# stm32f4stampV1_3_1.net
KiCad netlist of a schematic drawn in EAGLE
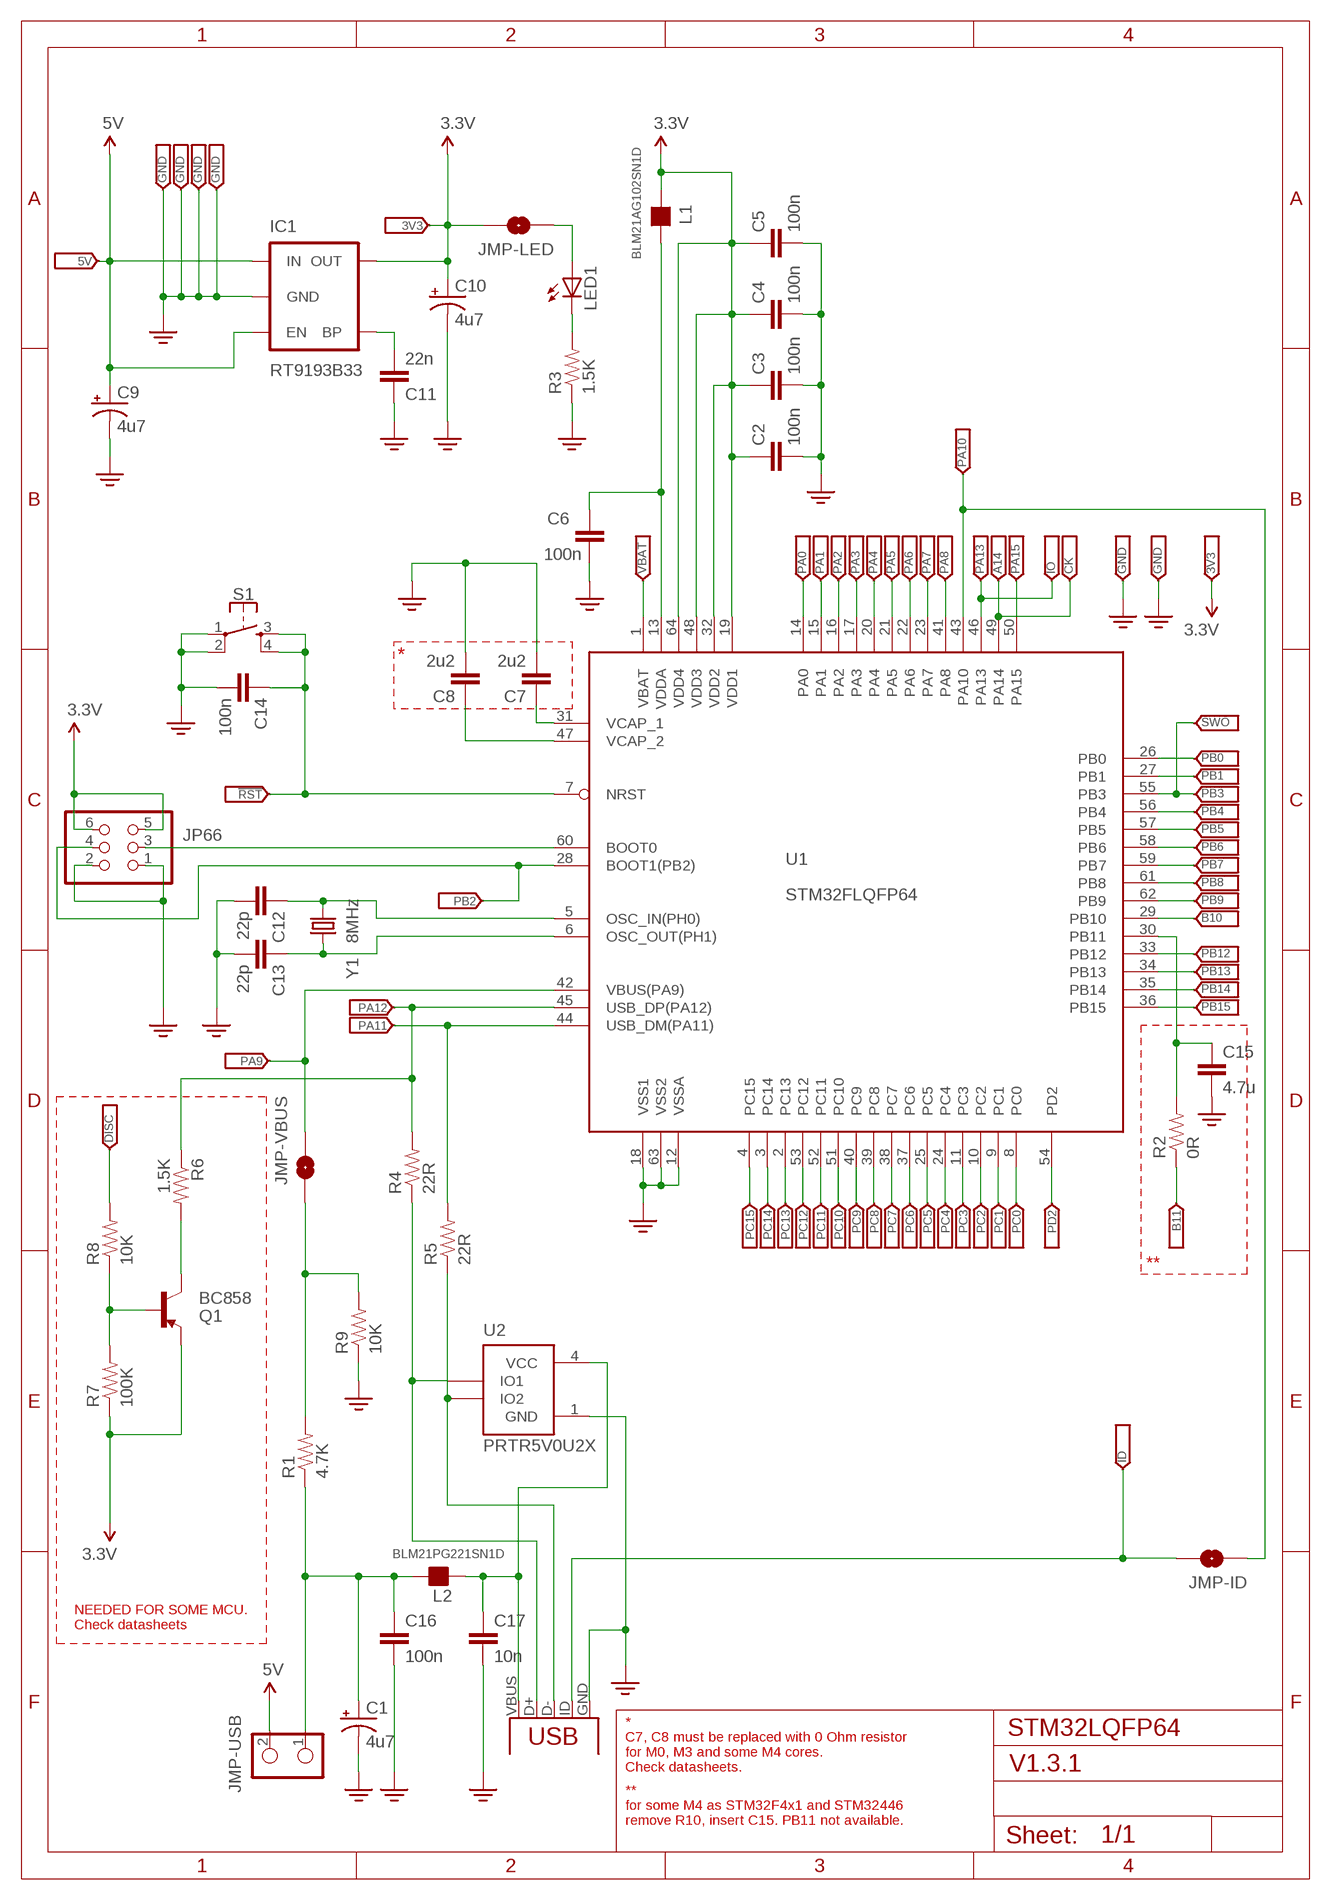
[diagram p0: schematic, sheet 1]

(export (version "E")
  (design (tool "Eeschema 10.0.6"))
  (components
    (comp (ref "C1")
      (value "4u7")
      (footprint "eagle-import:EIA3216-KIT")
      (libsource (lib "eagle-import") (part "CAP_POL1206-KIT"))
    )
    (comp (ref "C2")
      (value "100n")
      (footprint "eagle-import:0805")
      (libsource (lib "eagle-import") (part "CAP0805"))
    )
    (comp (ref "C3")
      (value "100n")
      (footprint "eagle-import:0805")
      (libsource (lib "eagle-import") (part "CAP0805"))
    )
    (comp (ref "C4")
      (value "100n")
      (footprint "eagle-import:0805")
      (libsource (lib "eagle-import") (part "CAP0805"))
    )
    (comp (ref "C5")
      (value "100n")
      (footprint "eagle-import:0805")
      (libsource (lib "eagle-import") (part "CAP0805"))
    )
    (comp (ref "C6")
      (value "100n")
      (footprint "eagle-import:0805")
      (libsource (lib "eagle-import") (part "CAP0805"))
    )
    (comp (ref "C7")
      (value "2u2")
      (footprint "eagle-import:0805")
      (libsource (lib "eagle-import") (part "CAP0805"))
    )
    (comp (ref "C8")
      (value "2u2")
      (footprint "eagle-import:0805")
      (libsource (lib "eagle-import") (part "CAP0805"))
    )
    (comp (ref "C9")
      (value "4u7")
      (footprint "eagle-import:EIA3216-KIT")
      (libsource (lib "eagle-import") (part "CAP_POL1206-KIT"))
    )
    (comp (ref "C10")
      (value "4u7")
      (footprint "eagle-import:EIA3216-KIT")
      (libsource (lib "eagle-import") (part "CAP_POL1206-KIT"))
    )
    (comp (ref "C11")
      (value "22n")
      (footprint "eagle-import:0805")
      (libsource (lib "eagle-import") (part "CAP0805"))
    )
    (comp (ref "C12")
      (value "22p")
      (footprint "eagle-import:0805")
      (libsource (lib "eagle-import") (part "CAP0805"))
    )
    (comp (ref "C13")
      (value "22p")
      (footprint "eagle-import:0805")
      (libsource (lib "eagle-import") (part "CAP0805"))
    )
    (comp (ref "C14")
      (value "100n")
      (footprint "eagle-import:0805")
      (libsource (lib "eagle-import") (part "CAP0805"))
    )
    (comp (ref "C15")
      (value "4.7u")
      (footprint "eagle-import:0805")
      (libsource (lib "eagle-import") (part "CAP0805"))
    )
    (comp (ref "C16")
      (value "100n")
      (footprint "eagle-import:0805")
      (libsource (lib "eagle-import") (part "CAP0805"))
    )
    (comp (ref "C17")
      (value "10n")
      (footprint "eagle-import:0805")
      (libsource (lib "eagle-import") (part "CAP0805"))
    )
    (comp (ref "IC1")
      (value "RT9193B33")
      (footprint "eagle-import:SOT23-5")
      (libsource (lib "eagle-import") (part "V_REG_LDOSMD"))
    )
    (comp (ref "JMP-ID")
      (value "SOLDERJUMPERNO")
      (footprint "eagle-import:SJ_2S-NO")
      (libsource (lib "eagle-import") (part "SOLDERJUMPERNO"))
    )
    (comp (ref "JMP-LED")
      (value "SOLDERJUMPERNO")
      (footprint "eagle-import:SJ_2S-NO")
      (libsource (lib "eagle-import") (part "SOLDERJUMPERNO"))
    )
    (comp (ref "JMP-USB")
      (value "JUMPER-2PTH")
      (footprint "eagle-import:1X02")
      (libsource (lib "eagle-import") (part "JUMPER-2PTH"))
    )
    (comp (ref "JMP-VBUS")
      (value "SOLDERJUMPERNO")
      (footprint "eagle-import:SJ_2S-NO")
      (libsource (lib "eagle-import") (part "SOLDERJUMPERNO"))
    )
    (comp (ref "JP1")
      (value "PA12")
      (footprint "eagle-import:1X1-HEADER-HOLE")
      (libsource (lib "eagle-import") (part "HEADERHOLE-HEADERHOLE"))
    )
    (comp (ref "JP2")
      (value "5V")
      (footprint "eagle-import:1X1-HEADER-HOLE")
      (libsource (lib "eagle-import") (part "HEADERHOLE-HEADERHOLE"))
    )
    (comp (ref "JP3")
      (value "GND")
      (footprint "eagle-import:1X1-HEADER-HOLE")
      (libsource (lib "eagle-import") (part "HEADERHOLE-HEADERHOLE"))
    )
    (comp (ref "JP4")
      (value "3V3")
      (footprint "eagle-import:1X1-HEADER-HOLE")
      (libsource (lib "eagle-import") (part "HEADERHOLE-HEADERHOLE"))
    )
    (comp (ref "JP5")
      (value "DISC")
      (footprint "eagle-import:1X1-HEADER-HOLE")
      (libsource (lib "eagle-import") (part "HEADERHOLE-HEADERHOLE"))
    )
    (comp (ref "JP6")
      (value "GND")
      (footprint "eagle-import:1X1-HEADER-HOLE")
      (libsource (lib "eagle-import") (part "HEADERHOLE-HEADERHOLE"))
    )
    (comp (ref "JP7")
      (value "GND")
      (footprint "eagle-import:1X1-HEADER-HOLE")
      (libsource (lib "eagle-import") (part "HEADERHOLE-HEADERHOLE"))
    )
    (comp (ref "JP8")
      (value "PB8")
      (footprint "eagle-import:1X1-HEADER-HOLE")
      (libsource (lib "eagle-import") (part "HEADERHOLE-HEADERHOLE"))
    )
    (comp (ref "JP9")
      (value "PA10")
      (footprint "eagle-import:1X1-HEADER-HOLE")
      (libsource (lib "eagle-import") (part "HEADERHOLE-HEADERHOLE"))
    )
    (comp (ref "JP10")
      (value "PA8")
      (footprint "eagle-import:1X1-HEADER-HOLE")
      (libsource (lib "eagle-import") (part "HEADERHOLE-HEADERHOLE"))
    )
    (comp (ref "JP11")
      (value "PA13")
      (footprint "eagle-import:1X1-HEADER-HOLE")
      (libsource (lib "eagle-import") (part "HEADERHOLE-HEADERHOLE"))
    )
    (comp (ref "JP12")
      (value "PC9")
      (footprint "eagle-import:1X1-HEADER-HOLE")
      (libsource (lib "eagle-import") (part "HEADERHOLE-HEADERHOLE"))
    )
    (comp (ref "JP13")
      (value "PC15")
      (footprint "eagle-import:1X1-HEADER-HOLE")
      (libsource (lib "eagle-import") (part "HEADERHOLE-HEADERHOLE"))
    )
    (comp (ref "JP14")
      (value "PC14")
      (footprint "eagle-import:1X1-HEADER-HOLE")
      (libsource (lib "eagle-import") (part "HEADERHOLE-HEADERHOLE"))
    )
    (comp (ref "JP15")
      (value "PC13")
      (footprint "eagle-import:1X1-HEADER-HOLE")
      (libsource (lib "eagle-import") (part "HEADERHOLE-HEADERHOLE"))
    )
    (comp (ref "JP16")
      (value "PC12")
      (footprint "eagle-import:1X1-HEADER-HOLE")
      (libsource (lib "eagle-import") (part "HEADERHOLE-HEADERHOLE"))
    )
    (comp (ref "JP17")
      (value "PC11")
      (footprint "eagle-import:1X1-HEADER-HOLE")
      (libsource (lib "eagle-import") (part "HEADERHOLE-HEADERHOLE"))
    )
    (comp (ref "JP18")
      (value "PC10")
      (footprint "eagle-import:1X1-HEADER-HOLE")
      (libsource (lib "eagle-import") (part "HEADERHOLE-HEADERHOLE"))
    )
    (comp (ref "JP19")
      (value "PC8")
      (footprint "eagle-import:1X1-HEADER-HOLE")
      (libsource (lib "eagle-import") (part "HEADERHOLE-HEADERHOLE"))
    )
    (comp (ref "JP20")
      (value "PC7")
      (footprint "eagle-import:1X1-HEADER-HOLE")
      (libsource (lib "eagle-import") (part "HEADERHOLE-HEADERHOLE"))
    )
    (comp (ref "JP21")
      (value "PC6")
      (footprint "eagle-import:1X1-HEADER-HOLE")
      (libsource (lib "eagle-import") (part "HEADERHOLE-HEADERHOLE"))
    )
    (comp (ref "JP22")
      (value "PC5")
      (footprint "eagle-import:1X1-HEADER-HOLE")
      (libsource (lib "eagle-import") (part "HEADERHOLE-HEADERHOLE"))
    )
    (comp (ref "JP23")
      (value "PC4")
      (footprint "eagle-import:1X1-HEADER-HOLE")
      (libsource (lib "eagle-import") (part "HEADERHOLE-HEADERHOLE"))
    )
    (comp (ref "JP24")
      (value "PC3")
      (footprint "eagle-import:1X1-HEADER-HOLE")
      (libsource (lib "eagle-import") (part "HEADERHOLE-HEADERHOLE"))
    )
    (comp (ref "JP25")
      (value "PC2")
      (footprint "eagle-import:1X1-HEADER-HOLE")
      (libsource (lib "eagle-import") (part "HEADERHOLE-HEADERHOLE"))
    )
    (comp (ref "JP26")
      (value "PC1")
      (footprint "eagle-import:1X1-HEADER-HOLE")
      (libsource (lib "eagle-import") (part "HEADERHOLE-HEADERHOLE"))
    )
    (comp (ref "JP27")
      (value "PC0")
      (footprint "eagle-import:1X1-HEADER-HOLE")
      (libsource (lib "eagle-import") (part "HEADERHOLE-HEADERHOLE"))
    )
    (comp (ref "JP28")
      (value "PD2")
      (footprint "eagle-import:1X1-HEADER-HOLE")
      (libsource (lib "eagle-import") (part "HEADERHOLE-HEADERHOLE"))
    )
    (comp (ref "JP29")
      (value "PA0")
      (footprint "eagle-import:1X1-HEADER-HOLE")
      (libsource (lib "eagle-import") (part "HEADERHOLE-HEADERHOLE"))
    )
    (comp (ref "JP30")
      (value "PA1")
      (footprint "eagle-import:1X1-HEADER-HOLE")
      (libsource (lib "eagle-import") (part "HEADERHOLE-HEADERHOLE"))
    )
    (comp (ref "JP31")
      (value "PA2")
      (footprint "eagle-import:1X1-HEADER-HOLE")
      (libsource (lib "eagle-import") (part "HEADERHOLE-HEADERHOLE"))
    )
    (comp (ref "JP32")
      (value "PA3")
      (footprint "eagle-import:1X1-HEADER-HOLE")
      (libsource (lib "eagle-import") (part "HEADERHOLE-HEADERHOLE"))
    )
    (comp (ref "JP33")
      (value "PA4")
      (footprint "eagle-import:1X1-HEADER-HOLE")
      (libsource (lib "eagle-import") (part "HEADERHOLE-HEADERHOLE"))
    )
    (comp (ref "JP34")
      (value "PA5")
      (footprint "eagle-import:1X1-HEADER-HOLE")
      (libsource (lib "eagle-import") (part "HEADERHOLE-HEADERHOLE"))
    )
    (comp (ref "JP35")
      (value "PA6")
      (footprint "eagle-import:1X1-HEADER-HOLE")
      (libsource (lib "eagle-import") (part "HEADERHOLE-HEADERHOLE"))
    )
    (comp (ref "JP36")
      (value "PA7")
      (footprint "eagle-import:1X1-HEADER-HOLE")
      (libsource (lib "eagle-import") (part "HEADERHOLE-HEADERHOLE"))
    )
    (comp (ref "JP37")
      (value "A14")
      (footprint "eagle-import:1X1-HEADER-HOLE")
      (libsource (lib "eagle-import") (part "HEADERHOLE-HEADERHOLE"))
    )
    (comp (ref "JP38")
      (value "PA15")
      (footprint "eagle-import:1X1-HEADER-HOLE")
      (libsource (lib "eagle-import") (part "HEADERHOLE-HEADERHOLE"))
    )
    (comp (ref "JP39")
      (value "PB0")
      (footprint "eagle-import:1X1-HEADER-HOLE")
      (libsource (lib "eagle-import") (part "HEADERHOLE-HEADERHOLE"))
    )
    (comp (ref "JP40")
      (value "PB1")
      (footprint "eagle-import:1X1-HEADER-HOLE")
      (libsource (lib "eagle-import") (part "HEADERHOLE-HEADERHOLE"))
    )
    (comp (ref "JP41")
      (value "PB3")
      (footprint "eagle-import:1X1-HEADER-HOLE")
      (libsource (lib "eagle-import") (part "HEADERHOLE-HEADERHOLE"))
    )
    (comp (ref "JP42")
      (value "PB4")
      (footprint "eagle-import:1X1-HEADER-HOLE")
      (libsource (lib "eagle-import") (part "HEADERHOLE-HEADERHOLE"))
    )
    (comp (ref "JP43")
      (value "PB5")
      (footprint "eagle-import:1X1-HEADER-HOLE")
      (libsource (lib "eagle-import") (part "HEADERHOLE-HEADERHOLE"))
    )
    (comp (ref "JP44")
      (value "PB6")
      (footprint "eagle-import:1X1-HEADER-HOLE")
      (libsource (lib "eagle-import") (part "HEADERHOLE-HEADERHOLE"))
    )
    (comp (ref "JP45")
      (value "PB7")
      (footprint "eagle-import:1X1-HEADER-HOLE")
      (libsource (lib "eagle-import") (part "HEADERHOLE-HEADERHOLE"))
    )
    (comp (ref "JP46")
      (value "PB9")
      (footprint "eagle-import:1X1-HEADER-HOLE")
      (libsource (lib "eagle-import") (part "HEADERHOLE-HEADERHOLE"))
    )
    (comp (ref "JP47")
      (value "B10")
      (footprint "eagle-import:1X1-HEADER-HOLE")
      (libsource (lib "eagle-import") (part "HEADERHOLE-HEADERHOLE"))
    )
    (comp (ref "JP48")
      (value "B11")
      (footprint "eagle-import:1X1-HEADER-HOLE")
      (libsource (lib "eagle-import") (part "HEADERHOLE-HEADERHOLE"))
    )
    (comp (ref "JP49")
      (value "PB12")
      (footprint "eagle-import:1X1-HEADER-HOLE")
      (libsource (lib "eagle-import") (part "HEADERHOLE-HEADERHOLE"))
    )
    (comp (ref "JP50")
      (value "PB13")
      (footprint "eagle-import:1X1-HEADER-HOLE")
      (libsource (lib "eagle-import") (part "HEADERHOLE-HEADERHOLE"))
    )
    (comp (ref "JP51")
      (value "PB14")
      (footprint "eagle-import:1X1-HEADER-HOLE")
      (libsource (lib "eagle-import") (part "HEADERHOLE-HEADERHOLE"))
    )
    (comp (ref "JP52")
      (value "PB15")
      (footprint "eagle-import:1X1-HEADER-HOLE")
      (libsource (lib "eagle-import") (part "HEADERHOLE-HEADERHOLE"))
    )
    (comp (ref "JP53")
      (value "VBAT")
      (footprint "eagle-import:1X1-HEADER-HOLE")
      (libsource (lib "eagle-import") (part "HEADERHOLE-HEADERHOLE"))
    )
    (comp (ref "JP54")
      (value "!RST")
      (footprint "eagle-import:1X1-HEADER-HOLE")
      (libsource (lib "eagle-import") (part "HEADERHOLE-HEADERHOLE"))
    )
    (comp (ref "JP55")
      (value "GND")
      (footprint "eagle-import:1X1-HEADER-HOLE")
      (libsource (lib "eagle-import") (part "HEADERHOLE-HEADERHOLE"))
    )
    (comp (ref "JP56")
      (value "ID")
      (footprint "eagle-import:1X1-HEADER-HOLE")
      (libsource (lib "eagle-import") (part "HEADERHOLE-HEADERHOLE"))
    )
    (comp (ref "JP57")
      (value "PB2")
      (footprint "eagle-import:1X1-HEADER-HOLE")
      (libsource (lib "eagle-import") (part "HEADERHOLE-HEADERHOLE"))
    )
    (comp (ref "JP58")
      (value "PA11")
      (footprint "eagle-import:1X1-HEADER-HOLE")
      (libsource (lib "eagle-import") (part "HEADERHOLE-HEADERHOLE"))
    )
    (comp (ref "JP59")
      (value "IO")
      (footprint "eagle-import:1X1-HEADER-HOLE")
      (libsource (lib "eagle-import") (part "HEADERHOLE-HEADERHOLE"))
    )
    (comp (ref "JP60")
      (value "CK")
      (footprint "eagle-import:1X1-HEADER-HOLE")
      (libsource (lib "eagle-import") (part "HEADERHOLE-HEADERHOLE"))
    )
    (comp (ref "JP61")
      (value "SWO")
      (footprint "eagle-import:1X1-HEADER-HOLE")
      (libsource (lib "eagle-import") (part "HEADERHOLE-HEADERHOLE"))
    )
    (comp (ref "JP62")
      (value "GND")
      (footprint "eagle-import:1X1-HEADER-HOLE")
      (libsource (lib "eagle-import") (part "HEADERHOLE-HEADERHOLE"))
    )
    (comp (ref "JP63")
      (value "3V3")
      (footprint "eagle-import:1X1-HEADER-HOLE")
      (libsource (lib "eagle-import") (part "HEADERHOLE-HEADERHOLE"))
    )
    (comp (ref "JP64")
      (value "PA9")
      (footprint "eagle-import:1X1-HEADER-HOLE")
      (libsource (lib "eagle-import") (part "HEADERHOLE-HEADERHOLE"))
    )
    (comp (ref "JP65")
      (value "GND")
      (footprint "eagle-import:1X1-HEADER-HOLE")
      (libsource (lib "eagle-import") (part "HEADERHOLE-HEADERHOLE"))
    )
    (comp (ref "JP66")
      (value "PINHD-2X3")
      (footprint "eagle-import:2X03")
      (libsource (lib "eagle-import") (part "PINHD-2X3"))
    )
    (comp (ref "L1")
      (value "BLM21AG102SN1D")
      (footprint "eagle-import:L0805")
      (libsource (lib "eagle-import") (part "FB_0805"))
    )
    (comp (ref "L2")
      (value "BLM21PG221SN1D")
      (footprint "eagle-import:L0805")
      (libsource (lib "eagle-import") (part "FB_0805"))
    )
    (comp (ref "LED1")
      (value "LEDSML0805")
      (footprint "eagle-import:SML0805")
      (libsource (lib "eagle-import") (part "LEDSML0805"))
    )
    (comp (ref "Q1")
      (value "BC858")
      (footprint "eagle-import:SOT23-3")
      (libsource (lib "eagle-import") (part "TRANSISTOR_PNPSMD"))
    )
    (comp (ref "R1")
      (value "4.7K")
      (footprint "eagle-import:0805")
      (libsource (lib "eagle-import") (part "RESISTOR0805-RES"))
    )
    (comp (ref "R2")
      (value "0R")
      (footprint "eagle-import:0805")
      (libsource (lib "eagle-import") (part "RESISTOR0805-RES"))
    )
    (comp (ref "R3")
      (value "1.5K")
      (footprint "eagle-import:0805")
      (libsource (lib "eagle-import") (part "RESISTOR0805-RES"))
    )
    (comp (ref "R4")
      (value "22R")
      (footprint "eagle-import:0805")
      (libsource (lib "eagle-import") (part "RESISTOR0805-RES"))
    )
    (comp (ref "R5")
      (value "22R")
      (footprint "eagle-import:0805")
      (libsource (lib "eagle-import") (part "RESISTOR0805-RES"))
    )
    (comp (ref "R6")
      (value "1.5K")
      (footprint "eagle-import:0805")
      (libsource (lib "eagle-import") (part "RESISTOR0805-RES"))
    )
    (comp (ref "R7")
      (value "100K")
      (footprint "eagle-import:0805")
      (libsource (lib "eagle-import") (part "RESISTOR0805-RES"))
    )
    (comp (ref "R8")
      (value "10K")
      (footprint "eagle-import:0805")
      (libsource (lib "eagle-import") (part "RESISTOR0805-RES"))
    )
    (comp (ref "R9")
      (value "10K")
      (footprint "eagle-import:0805")
      (libsource (lib "eagle-import") (part "RESISTOR0805-RES"))
    )
    (comp (ref "S1")
      (value "MOMENTARY-SWITCH-SPST-2-SMD-5.2MM")
      (footprint "eagle-import:TACTILE_SWITCH_SMD_5.2MM")
      (libsource (lib "eagle-import") (part "MOMENTARY-SWITCH-SPST-2-SMD-5.2MM"))
    )
    (comp (ref "U1")
      (value "STM32FLQFP64")
      (footprint "eagle-import:LQFP64")
      (libsource (lib "eagle-import") (part "STM32F405RGT"))
    )
    (comp (ref "U2")
      (value "PRTR5V0U2X")
      (footprint "eagle-import:SOT-143B")
      (fields
        (field (name "MANUFACTURER") "NXP Semiconductors")
        (field (name "PART_NUMBER") "PRTR5V0U2X,215")
      )
      (libsource (lib "eagle-import") (part "PRTR5V0U2X?"))
    )
    (comp (ref "USB")
      (value "USB-MICROB-SMD")
      (footprint "eagle-import:USB-MICROB-SMD")
      (libsource (lib "eagle-import") (part "USB-MICROB-SMD"))
    )
    (comp (ref "Y1")
      (value "8MHz")
      (footprint "eagle-import:CRYSTAL-SMD-5X3")
      (libsource (lib "eagle-import") (part "CRYSTAL5X3"))
    )
  )
  (nets
    (net (code "1") (name "3.3V") (class "Default")
      (node (ref "C10") (pin "A") (pinfunction "+_A") (pintype "passive"))
      (node (ref "C2") (pin "1") (pinfunction "1_1") (pintype "passive"))
      (node (ref "C3") (pin "1") (pinfunction "1_1") (pintype "passive"))
      (node (ref "C4") (pin "1") (pinfunction "1_1") (pintype "passive"))
      (node (ref "C5") (pin "1") (pinfunction "1_1") (pintype "passive"))
      (node (ref "IC1") (pin "5") (pinfunction "OUT_5") (pintype "passive"))
      (node (ref "JMP-LED") (pin "2") (pinfunction "2_2") (pintype "passive"))
      (node (ref "JP4") (pin "1") (pinfunction "P$1_1") (pintype "bidirectional"))
      (node (ref "JP63") (pin "1") (pinfunction "P$1_1") (pintype "bidirectional"))
      (node (ref "JP66") (pin "5") (pinfunction "5_5") (pintype "passive"))
      (node (ref "JP66") (pin "6") (pinfunction "6_6") (pintype "passive"))
      (node (ref "L1") (pin "2") (pinfunction "2_2") (pintype "passive"))
      (node (ref "Q1") (pin "2") (pinfunction "E_2") (pintype "passive"))
      (node (ref "R7") (pin "1") (pinfunction "1_1") (pintype "passive"))
      (node (ref "U1") (pin "19") (pinfunction "VDD1_19") (pintype "power_in"))
      (node (ref "U1") (pin "32") (pinfunction "VDD2_32") (pintype "power_in"))
      (node (ref "U1") (pin "48") (pinfunction "VDD3_48") (pintype "power_in"))
      (node (ref "U1") (pin "64") (pinfunction "VDD4_64") (pintype "power_in"))
    )
    (net (code "2") (name "5V") (class "Default")
      (node (ref "C9") (pin "A") (pinfunction "+_A") (pintype "passive"))
      (node (ref "IC1") (pin "1") (pinfunction "IN_1") (pintype "input"))
      (node (ref "IC1") (pin "3") (pinfunction "EN_3") (pintype "input"))
      (node (ref "JMP-USB") (pin "2") (pinfunction "2_2") (pintype "passive"))
      (node (ref "JP2") (pin "1") (pinfunction "P$1_1") (pintype "bidirectional"))
    )
    (net (code "3") (name "GND") (class "Default")
      (node (ref "C1") (pin "C") (pinfunction "-_C") (pintype "passive"))
      (node (ref "C10") (pin "C") (pinfunction "-_C") (pintype "passive"))
      (node (ref "C11") (pin "1") (pinfunction "1_1") (pintype "passive"))
      (node (ref "C12") (pin "2") (pinfunction "2_2") (pintype "passive"))
      (node (ref "C13") (pin "2") (pinfunction "2_2") (pintype "passive"))
      (node (ref "C14") (pin "2") (pinfunction "2_2") (pintype "passive"))
      (node (ref "C15") (pin "2") (pinfunction "2_2") (pintype "passive"))
      (node (ref "C16") (pin "2") (pinfunction "2_2") (pintype "passive"))
      (node (ref "C17") (pin "2") (pinfunction "2_2") (pintype "passive"))
      (node (ref "C2") (pin "2") (pinfunction "2_2") (pintype "passive"))
      (node (ref "C3") (pin "2") (pinfunction "2_2") (pintype "passive"))
      (node (ref "C4") (pin "2") (pinfunction "2_2") (pintype "passive"))
      (node (ref "C5") (pin "2") (pinfunction "2_2") (pintype "passive"))
      (node (ref "C6") (pin "2") (pinfunction "2_2") (pintype "passive"))
      (node (ref "C7") (pin "2") (pinfunction "2_2") (pintype "passive"))
      (node (ref "C8") (pin "2") (pinfunction "2_2") (pintype "passive"))
      (node (ref "C9") (pin "C") (pinfunction "-_C") (pintype "passive"))
      (node (ref "IC1") (pin "2") (pinfunction "GND_2") (pintype "input"))
      (node (ref "JP3") (pin "1") (pinfunction "P$1_1") (pintype "bidirectional"))
      (node (ref "JP55") (pin "1") (pinfunction "P$1_1") (pintype "bidirectional"))
      (node (ref "JP6") (pin "1") (pinfunction "P$1_1") (pintype "bidirectional"))
      (node (ref "JP62") (pin "1") (pinfunction "P$1_1") (pintype "bidirectional"))
      (node (ref "JP65") (pin "1") (pinfunction "P$1_1") (pintype "bidirectional"))
      (node (ref "JP66") (pin "1") (pinfunction "1_1") (pintype "passive"))
      (node (ref "JP66") (pin "2") (pinfunction "2_2") (pintype "passive"))
      (node (ref "JP7") (pin "1") (pinfunction "P$1_1") (pintype "bidirectional"))
      (node (ref "R3") (pin "1") (pinfunction "1_1") (pintype "passive"))
      (node (ref "R9") (pin "1") (pinfunction "1_1") (pintype "passive"))
      (node (ref "S1") (pin "1") (pinfunction "1_1") (pintype "passive"))
      (node (ref "S1") (pin "2") (pinfunction "2_2") (pintype "passive"))
      (node (ref "U1") (pin "12") (pinfunction "VSSA_12") (pintype "power_in"))
      (node (ref "U1") (pin "18") (pinfunction "VSS1_18") (pintype "power_in"))
      (node (ref "U1") (pin "63") (pinfunction "VSS2_63") (pintype "power_in"))
      (node (ref "U2") (pin "1") (pinfunction "GND_1") (pintype "bidirectional"))
      (node (ref "USB") (pin "GND") (pinfunction "GND_GND") (pintype "bidirectional"))
      (node (ref "USB") (pin "MT1") (pinfunction "P$1_MT1") (pintype "bidirectional"))
      (node (ref "USB") (pin "MT2") (pinfunction "P$1_MT2") (pintype "bidirectional"))
      (node (ref "USB") (pin "MT3") (pinfunction "P$1_MT3") (pintype "bidirectional"))
      (node (ref "USB") (pin "MT4") (pinfunction "P$1_MT4") (pintype "bidirectional"))
    )
    (net (code "4") (name "Net-(C1-+)") (class "Default")
      (node (ref "C1") (pin "A") (pinfunction "+_A") (pintype "passive"))
      (node (ref "C16") (pin "1") (pinfunction "1_1") (pintype "passive"))
      (node (ref "JMP-USB") (pin "1") (pinfunction "1_1") (pintype "passive"))
      (node (ref "L2") (pin "2") (pinfunction "2_2") (pintype "passive"))
      (node (ref "R1") (pin "1") (pinfunction "1_1") (pintype "passive"))
    )
    (net (code "5") (name "Net-(IC1-BP)") (class "Default")
      (node (ref "C11") (pin "2") (pinfunction "2_2") (pintype "passive"))
      (node (ref "IC1") (pin "4") (pinfunction "BP_4") (pintype "input"))
    )
    (net (code "6") (name "Net-(JMP-LED-Pad1)") (class "Default")
      (node (ref "JMP-LED") (pin "1") (pinfunction "1_1") (pintype "passive"))
      (node (ref "LED1") (pin "A") (pinfunction "A_A") (pintype "passive"))
    )
    (net (code "7") (name "Net-(JMP-VBUS-Pad1)") (class "Default")
      (node (ref "JMP-VBUS") (pin "1") (pinfunction "1_1") (pintype "passive"))
      (node (ref "R1") (pin "2") (pinfunction "2_2") (pintype "passive"))
      (node (ref "R9") (pin "2") (pinfunction "2_2") (pintype "passive"))
    )
    (net (code "8") (name "Net-(JP1-P$1)") (class "Default")
      (node (ref "JP1") (pin "1") (pinfunction "P$1_1") (pintype "bidirectional"))
      (node (ref "R4") (pin "2") (pinfunction "2_2") (pintype "passive"))
      (node (ref "R6") (pin "1") (pinfunction "1_1") (pintype "passive"))
      (node (ref "U1") (pin "45") (pinfunction "USB_DP(PA12)_45") (pintype "bidirectional"))
    )
    (net (code "9") (name "Net-(JP5-P$1)") (class "Default")
      (node (ref "JP5") (pin "1") (pinfunction "P$1_1") (pintype "bidirectional"))
      (node (ref "R8") (pin "2") (pinfunction "2_2") (pintype "passive"))
    )
    (net (code "10") (name "Net-(JP8-P$1)") (class "Default")
      (node (ref "JP8") (pin "1") (pinfunction "P$1_1") (pintype "bidirectional"))
      (node (ref "U1") (pin "61") (pinfunction "PB8_61") (pintype "bidirectional"))
    )
    (net (code "11") (name "Net-(JP9-P$1)") (class "Default")
      (node (ref "JMP-ID") (pin "1") (pinfunction "1_1") (pintype "passive"))
      (node (ref "JP9") (pin "1") (pinfunction "P$1_1") (pintype "bidirectional"))
      (node (ref "U1") (pin "43") (pinfunction "PA10_43") (pintype "bidirectional"))
    )
    (net (code "12") (name "Net-(JP10-P$1)") (class "Default")
      (node (ref "JP10") (pin "1") (pinfunction "P$1_1") (pintype "bidirectional"))
      (node (ref "U1") (pin "41") (pinfunction "PA8_41") (pintype "bidirectional"))
    )
    (net (code "13") (name "Net-(JP11-P$1)") (class "Default")
      (node (ref "JP11") (pin "1") (pinfunction "P$1_1") (pintype "bidirectional"))
      (node (ref "JP59") (pin "1") (pinfunction "P$1_1") (pintype "bidirectional"))
      (node (ref "U1") (pin "46") (pinfunction "PA13_46") (pintype "bidirectional"))
    )
    (net (code "14") (name "Net-(JP12-P$1)") (class "Default")
      (node (ref "JP12") (pin "1") (pinfunction "P$1_1") (pintype "bidirectional"))
      (node (ref "U1") (pin "40") (pinfunction "PC9_40") (pintype "bidirectional"))
    )
    (net (code "15") (name "Net-(JP13-P$1)") (class "Default")
      (node (ref "JP13") (pin "1") (pinfunction "P$1_1") (pintype "bidirectional"))
      (node (ref "U1") (pin "4") (pinfunction "PC15_4") (pintype "bidirectional"))
    )
    (net (code "16") (name "Net-(JP14-P$1)") (class "Default")
      (node (ref "JP14") (pin "1") (pinfunction "P$1_1") (pintype "bidirectional"))
      (node (ref "U1") (pin "3") (pinfunction "PC14_3") (pintype "bidirectional"))
    )
    (net (code "17") (name "Net-(JP15-P$1)") (class "Default")
      (node (ref "JP15") (pin "1") (pinfunction "P$1_1") (pintype "bidirectional"))
      (node (ref "U1") (pin "2") (pinfunction "PC13_2") (pintype "bidirectional"))
    )
    (net (code "18") (name "Net-(JP16-P$1)") (class "Default")
      (node (ref "JP16") (pin "1") (pinfunction "P$1_1") (pintype "bidirectional"))
      (node (ref "U1") (pin "53") (pinfunction "PC12_53") (pintype "bidirectional"))
    )
    (net (code "19") (name "Net-(JP17-P$1)") (class "Default")
      (node (ref "JP17") (pin "1") (pinfunction "P$1_1") (pintype "bidirectional"))
      (node (ref "U1") (pin "52") (pinfunction "PC11_52") (pintype "bidirectional"))
    )
    (net (code "20") (name "Net-(JP18-P$1)") (class "Default")
      (node (ref "JP18") (pin "1") (pinfunction "P$1_1") (pintype "bidirectional"))
      (node (ref "U1") (pin "51") (pinfunction "PC10_51") (pintype "bidirectional"))
    )
    (net (code "21") (name "Net-(JP19-P$1)") (class "Default")
      (node (ref "JP19") (pin "1") (pinfunction "P$1_1") (pintype "bidirectional"))
      (node (ref "U1") (pin "39") (pinfunction "PC8_39") (pintype "bidirectional"))
    )
    (net (code "22") (name "Net-(JP20-P$1)") (class "Default")
      (node (ref "JP20") (pin "1") (pinfunction "P$1_1") (pintype "bidirectional"))
      (node (ref "U1") (pin "38") (pinfunction "PC7_38") (pintype "bidirectional"))
    )
    (net (code "23") (name "Net-(JP21-P$1)") (class "Default")
      (node (ref "JP21") (pin "1") (pinfunction "P$1_1") (pintype "bidirectional"))
      (node (ref "U1") (pin "37") (pinfunction "PC6_37") (pintype "bidirectional"))
    )
    (net (code "24") (name "Net-(JP22-P$1)") (class "Default")
      (node (ref "JP22") (pin "1") (pinfunction "P$1_1") (pintype "bidirectional"))
      (node (ref "U1") (pin "25") (pinfunction "PC5_25") (pintype "bidirectional"))
    )
    (net (code "25") (name "Net-(JP23-P$1)") (class "Default")
      (node (ref "JP23") (pin "1") (pinfunction "P$1_1") (pintype "bidirectional"))
      (node (ref "U1") (pin "24") (pinfunction "PC4_24") (pintype "bidirectional"))
    )
    (net (code "26") (name "Net-(JP24-P$1)") (class "Default")
      (node (ref "JP24") (pin "1") (pinfunction "P$1_1") (pintype "bidirectional"))
      (node (ref "U1") (pin "11") (pinfunction "PC3_11") (pintype "bidirectional"))
    )
    (net (code "27") (name "Net-(JP25-P$1)") (class "Default")
      (node (ref "JP25") (pin "1") (pinfunction "P$1_1") (pintype "bidirectional"))
      (node (ref "U1") (pin "10") (pinfunction "PC2_10") (pintype "bidirectional"))
    )
    (net (code "28") (name "Net-(JP26-P$1)") (class "Default")
      (node (ref "JP26") (pin "1") (pinfunction "P$1_1") (pintype "bidirectional"))
      (node (ref "U1") (pin "9") (pinfunction "PC1_9") (pintype "bidirectional"))
    )
    (net (code "29") (name "Net-(JP27-P$1)") (class "Default")
      (node (ref "JP27") (pin "1") (pinfunction "P$1_1") (pintype "bidirectional"))
      (node (ref "U1") (pin "8") (pinfunction "PC0_8") (pintype "bidirectional"))
    )
    (net (code "30") (name "Net-(JP28-P$1)") (class "Default")
      (node (ref "JP28") (pin "1") (pinfunction "P$1_1") (pintype "bidirectional"))
      (node (ref "U1") (pin "54") (pinfunction "PD2_54") (pintype "bidirectional"))
    )
    (net (code "31") (name "Net-(JP29-P$1)") (class "Default")
      (node (ref "JP29") (pin "1") (pinfunction "P$1_1") (pintype "bidirectional"))
      (node (ref "U1") (pin "14") (pinfunction "PA0_14") (pintype "bidirectional"))
    )
    (net (code "32") (name "Net-(JP30-P$1)") (class "Default")
      (node (ref "JP30") (pin "1") (pinfunction "P$1_1") (pintype "bidirectional"))
      (node (ref "U1") (pin "15") (pinfunction "PA1_15") (pintype "bidirectional"))
    )
    (net (code "33") (name "Net-(JP31-P$1)") (class "Default")
      (node (ref "JP31") (pin "1") (pinfunction "P$1_1") (pintype "bidirectional"))
      (node (ref "U1") (pin "16") (pinfunction "PA2_16") (pintype "bidirectional"))
    )
    (net (code "34") (name "Net-(JP32-P$1)") (class "Default")
      (node (ref "JP32") (pin "1") (pinfunction "P$1_1") (pintype "bidirectional"))
      (node (ref "U1") (pin "17") (pinfunction "PA3_17") (pintype "bidirectional"))
    )
    (net (code "35") (name "Net-(JP33-P$1)") (class "Default")
      (node (ref "JP33") (pin "1") (pinfunction "P$1_1") (pintype "bidirectional"))
      (node (ref "U1") (pin "20") (pinfunction "PA4_20") (pintype "bidirectional"))
    )
    (net (code "36") (name "Net-(JP34-P$1)") (class "Default")
      (node (ref "JP34") (pin "1") (pinfunction "P$1_1") (pintype "bidirectional"))
      (node (ref "U1") (pin "21") (pinfunction "PA5_21") (pintype "bidirectional"))
    )
    (net (code "37") (name "Net-(JP35-P$1)") (class "Default")
      (node (ref "JP35") (pin "1") (pinfunction "P$1_1") (pintype "bidirectional"))
      (node (ref "U1") (pin "22") (pinfunction "PA6_22") (pintype "bidirectional"))
    )
    (net (code "38") (name "Net-(JP36-P$1)") (class "Default")
      (node (ref "JP36") (pin "1") (pinfunction "P$1_1") (pintype "bidirectional"))
      (node (ref "U1") (pin "23") (pinfunction "PA7_23") (pintype "bidirectional"))
    )
    (net (code "39") (name "Net-(JP37-P$1)") (class "Default")
      (node (ref "JP37") (pin "1") (pinfunction "P$1_1") (pintype "bidirectional"))
      (node (ref "JP60") (pin "1") (pinfunction "P$1_1") (pintype "bidirectional"))
      (node (ref "U1") (pin "49") (pinfunction "PA14_49") (pintype "bidirectional"))
    )
    (net (code "40") (name "Net-(JP38-P$1)") (class "Default")
      (node (ref "JP38") (pin "1") (pinfunction "P$1_1") (pintype "bidirectional"))
      (node (ref "U1") (pin "50") (pinfunction "PA15_50") (pintype "bidirectional"))
    )
    (net (code "41") (name "Net-(JP39-P$1)") (class "Default")
      (node (ref "JP39") (pin "1") (pinfunction "P$1_1") (pintype "bidirectional"))
      (node (ref "U1") (pin "26") (pinfunction "PB0_26") (pintype "bidirectional"))
    )
    (net (code "42") (name "Net-(JP40-P$1)") (class "Default")
      (node (ref "JP40") (pin "1") (pinfunction "P$1_1") (pintype "bidirectional"))
      (node (ref "U1") (pin "27") (pinfunction "PB1_27") (pintype "bidirectional"))
    )
    (net (code "43") (name "Net-(JP41-P$1)") (class "Default")
      (node (ref "JP41") (pin "1") (pinfunction "P$1_1") (pintype "bidirectional"))
      (node (ref "JP61") (pin "1") (pinfunction "P$1_1") (pintype "bidirectional"))
      (node (ref "U1") (pin "55") (pinfunction "PB3_55") (pintype "bidirectional"))
    )
    (net (code "44") (name "Net-(JP42-P$1)") (class "Default")
      (node (ref "JP42") (pin "1") (pinfunction "P$1_1") (pintype "bidirectional"))
      (node (ref "U1") (pin "56") (pinfunction "PB4_56") (pintype "bidirectional"))
    )
    (net (code "45") (name "Net-(JP43-P$1)") (class "Default")
      (node (ref "JP43") (pin "1") (pinfunction "P$1_1") (pintype "bidirectional"))
      (node (ref "U1") (pin "57") (pinfunction "PB5_57") (pintype "bidirectional"))
    )
    (net (code "46") (name "Net-(JP44-P$1)") (class "Default")
      (node (ref "JP44") (pin "1") (pinfunction "P$1_1") (pintype "bidirectional"))
      (node (ref "U1") (pin "58") (pinfunction "PB6_58") (pintype "bidirectional"))
    )
    (net (code "47") (name "Net-(JP45-P$1)") (class "Default")
      (node (ref "JP45") (pin "1") (pinfunction "P$1_1") (pintype "bidirectional"))
      (node (ref "U1") (pin "59") (pinfunction "PB7_59") (pintype "bidirectional"))
    )
    (net (code "48") (name "Net-(JP46-P$1)") (class "Default")
      (node (ref "JP46") (pin "1") (pinfunction "P$1_1") (pintype "bidirectional"))
      (node (ref "U1") (pin "62") (pinfunction "PB9_62") (pintype "bidirectional"))
    )
    (net (code "49") (name "Net-(JP47-P$1)") (class "Default")
      (node (ref "JP47") (pin "1") (pinfunction "P$1_1") (pintype "bidirectional"))
      (node (ref "U1") (pin "29") (pinfunction "PB10_29") (pintype "bidirectional"))
    )
    (net (code "50") (name "Net-(JP48-P$1)") (class "Default")
      (node (ref "JP48") (pin "1") (pinfunction "P$1_1") (pintype "bidirectional"))
      (node (ref "R2") (pin "1") (pinfunction "1_1") (pintype "passive"))
    )
    (net (code "51") (name "Net-(JP49-P$1)") (class "Default")
      (node (ref "JP49") (pin "1") (pinfunction "P$1_1") (pintype "bidirectional"))
      (node (ref "U1") (pin "33") (pinfunction "PB12_33") (pintype "bidirectional"))
    )
    (net (code "52") (name "Net-(JP50-P$1)") (class "Default")
      (node (ref "JP50") (pin "1") (pinfunction "P$1_1") (pintype "bidirectional"))
      (node (ref "U1") (pin "34") (pinfunction "PB13_34") (pintype "bidirectional"))
    )
    (net (code "53") (name "Net-(JP51-P$1)") (class "Default")
      (node (ref "JP51") (pin "1") (pinfunction "P$1_1") (pintype "bidirectional"))
      (node (ref "U1") (pin "35") (pinfunction "PB14_35") (pintype "bidirectional"))
    )
    (net (code "54") (name "Net-(JP52-P$1)") (class "Default")
      (node (ref "JP52") (pin "1") (pinfunction "P$1_1") (pintype "bidirectional"))
      (node (ref "U1") (pin "36") (pinfunction "PB15_36") (pintype "bidirectional"))
    )
    (net (code "55") (name "Net-(JP53-P$1)") (class "Default")
      (node (ref "JP53") (pin "1") (pinfunction "P$1_1") (pintype "bidirectional"))
      (node (ref "U1") (pin "1") (pinfunction "VBAT_1") (pintype "power_in"))
    )
    (net (code "56") (name "Net-(JP54-P$1)") (class "Default")
      (node (ref "C14") (pin "1") (pinfunction "1_1") (pintype "passive"))
      (node (ref "JP54") (pin "1") (pinfunction "P$1_1") (pintype "bidirectional"))
      (node (ref "S1") (pin "3") (pinfunction "3_3") (pintype "passive"))
      (node (ref "S1") (pin "4") (pinfunction "4_4") (pintype "passive"))
      (node (ref "U1") (pin "7") (pinfunction "NRST_7") (pintype "input"))
    )
    (net (code "57") (name "Net-(JP56-P$1)") (class "Default")
      (node (ref "JMP-ID") (pin "2") (pinfunction "2_2") (pintype "passive"))
      (node (ref "JP56") (pin "1") (pinfunction "P$1_1") (pintype "bidirectional"))
      (node (ref "USB") (pin "ID") (pinfunction "ID_ID") (pintype "bidirectional"))
    )
    (net (code "58") (name "Net-(JP57-P$1)") (class "Default")
      (node (ref "JP57") (pin "1") (pinfunction "P$1_1") (pintype "bidirectional"))
      (node (ref "JP66") (pin "4") (pinfunction "4_4") (pintype "passive"))
      (node (ref "U1") (pin "28") (pinfunction "BOOT1(PB2)_28") (pintype "input"))
    )
    (net (code "59") (name "Net-(JP58-P$1)") (class "Default")
      (node (ref "JP58") (pin "1") (pinfunction "P$1_1") (pintype "bidirectional"))
      (node (ref "R5") (pin "2") (pinfunction "2_2") (pintype "passive"))
      (node (ref "U1") (pin "44") (pinfunction "USB_DM(PA11)_44") (pintype "bidirectional"))
    )
    (net (code "60") (name "Net-(JP64-P$1)") (class "Default")
      (node (ref "JMP-VBUS") (pin "2") (pinfunction "2_2") (pintype "passive"))
      (node (ref "JP64") (pin "1") (pinfunction "P$1_1") (pintype "bidirectional"))
      (node (ref "U1") (pin "42") (pinfunction "VBUS(PA9)_42") (pintype "bidirectional"))
    )
    (net (code "61") (name "Net-(LED1-PadC)") (class "Default")
      (node (ref "LED1") (pin "C") (pinfunction "C_C") (pintype "passive"))
      (node (ref "R3") (pin "2") (pinfunction "2_2") (pintype "passive"))
    )
    (net (code "62") (name "Net-(Q1-B)") (class "Default")
      (node (ref "Q1") (pin "1") (pinfunction "B_1") (pintype "passive"))
      (node (ref "R7") (pin "2") (pinfunction "2_2") (pintype "passive"))
      (node (ref "R8") (pin "1") (pinfunction "1_1") (pintype "passive"))
    )
    (net (code "63") (name "Net-(Q1-C)") (class "Default")
      (node (ref "Q1") (pin "3") (pinfunction "C_3") (pintype "passive"))
      (node (ref "R6") (pin "2") (pinfunction "2_2") (pintype "passive"))
    )
    (net (code "64") (name "Net-(U1-BOOT0)") (class "Default")
      (node (ref "JP66") (pin "3") (pinfunction "3_3") (pintype "passive"))
      (node (ref "U1") (pin "60") (pinfunction "BOOT0_60") (pintype "input"))
    )
    (net (code "65") (name "Net-(U1-OSC_IN(PH0))") (class "Default")
      (node (ref "C12") (pin "1") (pinfunction "1_1") (pintype "passive"))
      (node (ref "U1") (pin "5") (pinfunction "OSC_IN(PH0)_5") (pintype "bidirectional"))
      (node (ref "Y1") (pin "3") (pinfunction "2_3") (pintype "passive"))
    )
    (net (code "66") (name "Net-(U1-OSC_OUT(PH1))") (class "Default")
      (node (ref "C13") (pin "1") (pinfunction "1_1") (pintype "passive"))
      (node (ref "U1") (pin "6") (pinfunction "OSC_OUT(PH1)_6") (pintype "bidirectional"))
      (node (ref "Y1") (pin "1") (pinfunction "1_1") (pintype "passive"))
    )
    (net (code "67") (name "Net-(U1-PB11)") (class "Default")
      (node (ref "C15") (pin "1") (pinfunction "1_1") (pintype "passive"))
      (node (ref "R2") (pin "2") (pinfunction "2_2") (pintype "passive"))
      (node (ref "U1") (pin "30") (pinfunction "PB11_30") (pintype "bidirectional"))
    )
    (net (code "68") (name "Net-(U1-VCAP_1)") (class "Default")
      (node (ref "C7") (pin "1") (pinfunction "1_1") (pintype "passive"))
      (node (ref "U1") (pin "31") (pinfunction "VCAP_1_31") (pintype "bidirectional"))
    )
    (net (code "69") (name "Net-(U1-VCAP_2)") (class "Default")
      (node (ref "C8") (pin "1") (pinfunction "1_1") (pintype "passive"))
      (node (ref "U1") (pin "47") (pinfunction "VCAP_2_47") (pintype "bidirectional"))
    )
    (net (code "70") (name "Net-(U1-VDDA)") (class "Default")
      (node (ref "C6") (pin "1") (pinfunction "1_1") (pintype "passive"))
      (node (ref "L1") (pin "1") (pinfunction "1_1") (pintype "passive"))
      (node (ref "U1") (pin "13") (pinfunction "VDDA_13") (pintype "power_in"))
    )
    (net (code "71") (name "Net-(U2-IO1)") (class "Default")
      (node (ref "R4") (pin "1") (pinfunction "1_1") (pintype "passive"))
      (node (ref "U2") (pin "2") (pinfunction "IO1_2") (pintype "bidirectional"))
      (node (ref "USB") (pin "D+") (pinfunction "D+_D+") (pintype "bidirectional"))
    )
    (net (code "72") (name "Net-(U2-IO2)") (class "Default")
      (node (ref "R5") (pin "1") (pinfunction "1_1") (pintype "passive"))
      (node (ref "U2") (pin "3") (pinfunction "IO2_3") (pintype "bidirectional"))
      (node (ref "USB") (pin "D-") (pinfunction "D-_D-") (pintype "bidirectional"))
    )
    (net (code "73") (name "Net-(U2-VCC)") (class "Default")
      (node (ref "C17") (pin "1") (pinfunction "1_1") (pintype "passive"))
      (node (ref "L2") (pin "1") (pinfunction "1_1") (pintype "passive"))
      (node (ref "U2") (pin "4") (pinfunction "VCC_4") (pintype "bidirectional"))
      (node (ref "USB") (pin "VBUS") (pinfunction "VBUS_VBUS") (pintype "bidirectional"))
    )
  )
)
